# RGBtlc.net
KiCad netlist of a schematic drawn in EAGLE
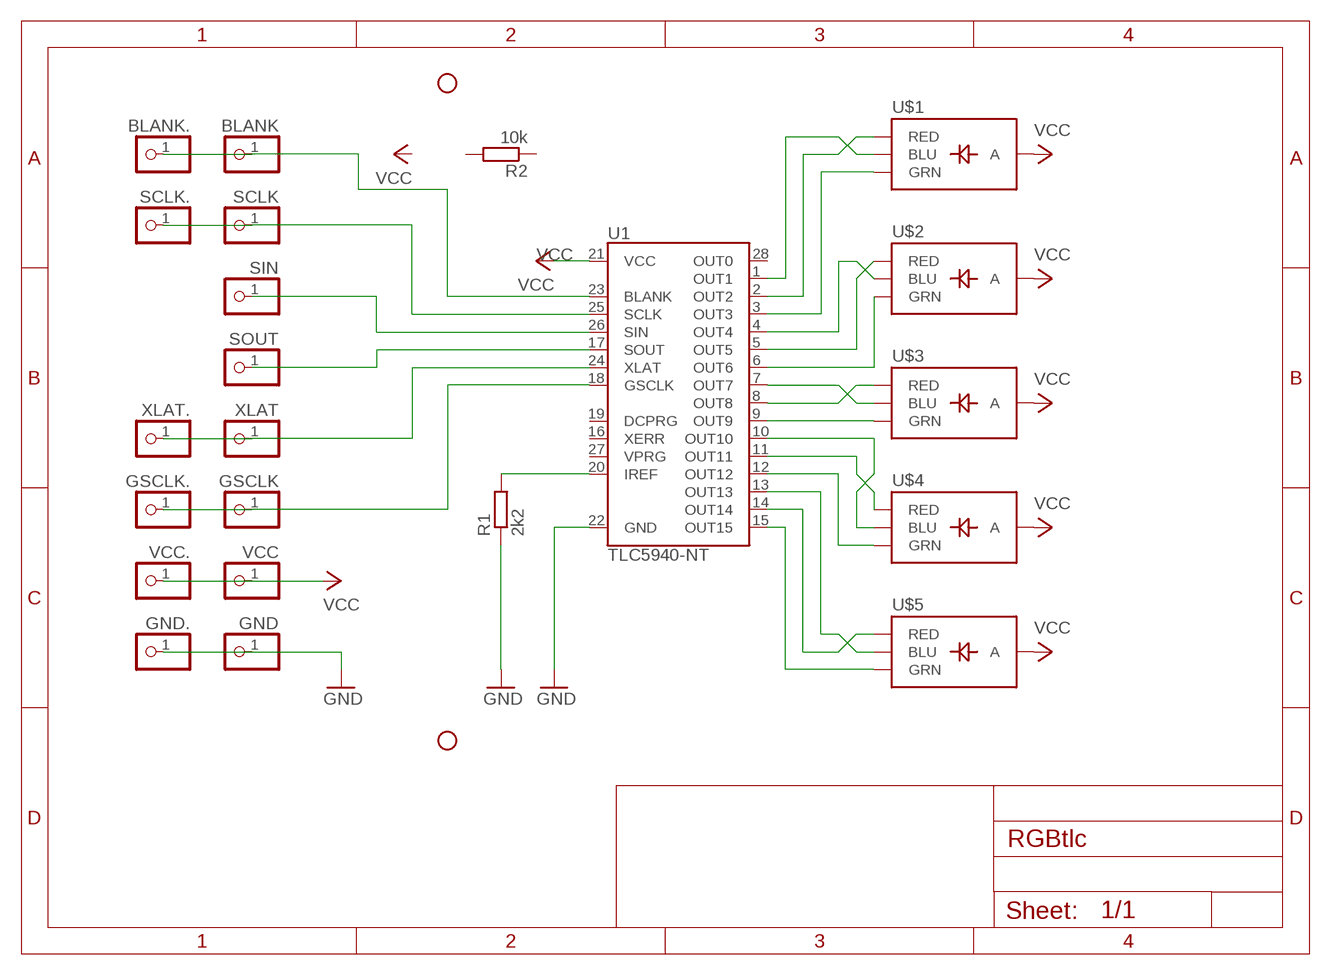
[diagram p0: schematic, sheet 1]

(export (version "E")
  (design (tool "Eeschema 10.0.6"))
  (components
    (comp (ref "BLANK")
      (value "PINHD-1X1")
      (footprint "eagle-import:1X01")
      (libsource (lib "eagle-import") (part "PINHD-1X1"))
    )
    (comp (ref "BLANK.")
      (value "PINHD-1X1")
      (footprint "eagle-import:1X01")
      (libsource (lib "eagle-import") (part "PINHD-1X1"))
    )
    (comp (ref "GND")
      (value "PINHD-1X1")
      (footprint "eagle-import:1X01")
      (libsource (lib "eagle-import") (part "PINHD-1X1"))
    )
    (comp (ref "GND.")
      (value "PINHD-1X1")
      (footprint "eagle-import:1X01")
      (libsource (lib "eagle-import") (part "PINHD-1X1"))
    )
    (comp (ref "GSCLK")
      (value "PINHD-1X1")
      (footprint "eagle-import:1X01")
      (libsource (lib "eagle-import") (part "PINHD-1X1"))
    )
    (comp (ref "GSCLK.")
      (value "PINHD-1X1")
      (footprint "eagle-import:1X01")
      (libsource (lib "eagle-import") (part "PINHD-1X1"))
    )
    (comp (ref "JP1")
      (value "STAND-OFF")
      (footprint "eagle-import:STAND-OFF")
      (libsource (lib "eagle-import") (part "STAND-OFF"))
    )
    (comp (ref "JP4")
      (value "STAND-OFF")
      (footprint "eagle-import:STAND-OFF")
      (libsource (lib "eagle-import") (part "STAND-OFF"))
    )
    (comp (ref "R1")
      (value "2k2")
      (footprint "eagle-import:0207_7")
      (libsource (lib "eagle-import") (part "R-EU_0207/7"))
    )
    (comp (ref "R2")
      (value "10k")
      (footprint "eagle-import:0207_7")
      (libsource (lib "eagle-import") (part "R-EU_0207/7"))
    )
    (comp (ref "SCLK")
      (value "PINHD-1X1")
      (footprint "eagle-import:1X01")
      (libsource (lib "eagle-import") (part "PINHD-1X1"))
    )
    (comp (ref "SCLK.")
      (value "PINHD-1X1")
      (footprint "eagle-import:1X01")
      (libsource (lib "eagle-import") (part "PINHD-1X1"))
    )
    (comp (ref "SIN")
      (value "PINHD-1X1")
      (footprint "eagle-import:1X01")
      (libsource (lib "eagle-import") (part "PINHD-1X1"))
    )
    (comp (ref "SOUT")
      (value "PINHD-1X1")
      (footprint "eagle-import:1X01")
      (libsource (lib "eagle-import") (part "PINHD-1X1"))
    )
    (comp (ref "U$1")
      (value "LED_PIRANHA_5MM")
      (footprint "eagle-import:LED_PIRANHA_5MM")
      (libsource (lib "eagle-import") (part "LED_PIRANHA_5MM"))
    )
    (comp (ref "U$2")
      (value "LED_PIRANHA_5MM")
      (footprint "eagle-import:LED_PIRANHA_5MM")
      (libsource (lib "eagle-import") (part "LED_PIRANHA_5MM"))
    )
    (comp (ref "U$3")
      (value "LED_PIRANHA_5MM")
      (footprint "eagle-import:LED_PIRANHA_5MM")
      (libsource (lib "eagle-import") (part "LED_PIRANHA_5MM"))
    )
    (comp (ref "U$4")
      (value "LED_PIRANHA_5MM")
      (footprint "eagle-import:LED_PIRANHA_5MM")
      (libsource (lib "eagle-import") (part "LED_PIRANHA_5MM"))
    )
    (comp (ref "U$5")
      (value "LED_PIRANHA_5MM")
      (footprint "eagle-import:LED_PIRANHA_5MM")
      (libsource (lib "eagle-import") (part "LED_PIRANHA_5MM"))
    )
    (comp (ref "U1")
      (value "TLC5940-NT")
      (footprint "eagle-import:DIL28-3")
      (libsource (lib "eagle-import") (part "TLC5940-NT"))
    )
    (comp (ref "VCC")
      (value "PINHD-1X1")
      (footprint "eagle-import:1X01")
      (libsource (lib "eagle-import") (part "PINHD-1X1"))
    )
    (comp (ref "VCC.")
      (value "PINHD-1X1")
      (footprint "eagle-import:1X01")
      (libsource (lib "eagle-import") (part "PINHD-1X1"))
    )
    (comp (ref "XLAT")
      (value "PINHD-1X1")
      (footprint "eagle-import:1X01")
      (libsource (lib "eagle-import") (part "PINHD-1X1"))
    )
    (comp (ref "XLAT.")
      (value "PINHD-1X1")
      (footprint "eagle-import:1X01")
      (libsource (lib "eagle-import") (part "PINHD-1X1"))
    )
  )
  (nets
    (net (code "1") (name "GND") (class "Default")
      (node (ref "GND") (pin "1") (pinfunction "1_1") (pintype "passive"))
      (node (ref "GND.") (pin "1") (pinfunction "1_1") (pintype "passive"))
      (node (ref "R1") (pin "1") (pinfunction "1_1") (pintype "passive"))
      (node (ref "U1") (pin "22") (pinfunction "GND_22") (pintype "bidirectional"))
    )
    (net (code "2") (name "Net-(U$1-BLU)") (class "Default")
      (node (ref "U$1") (pin "B") (pinfunction "BLU_B") (pintype "bidirectional"))
      (node (ref "U1") (pin "1") (pinfunction "OUT1_1") (pintype "bidirectional"))
    )
    (net (code "3") (name "Net-(U$1-GRN)") (class "Default")
      (node (ref "U$1") (pin "G") (pinfunction "GRN_G") (pintype "bidirectional"))
      (node (ref "U1") (pin "3") (pinfunction "OUT3_3") (pintype "bidirectional"))
    )
    (net (code "4") (name "Net-(U$1-RED)") (class "Default")
      (node (ref "U$1") (pin "R") (pinfunction "RED_R") (pintype "bidirectional"))
      (node (ref "U1") (pin "2") (pinfunction "OUT2_2") (pintype "bidirectional"))
    )
    (net (code "5") (name "Net-(U$2-BLU)") (class "Default")
      (node (ref "U$2") (pin "B") (pinfunction "BLU_B") (pintype "bidirectional"))
      (node (ref "U1") (pin "4") (pinfunction "OUT4_4") (pintype "bidirectional"))
    )
    (net (code "6") (name "Net-(U$2-GRN)") (class "Default")
      (node (ref "U$2") (pin "G") (pinfunction "GRN_G") (pintype "bidirectional"))
      (node (ref "U1") (pin "6") (pinfunction "OUT6_6") (pintype "bidirectional"))
    )
    (net (code "7") (name "Net-(U$2-RED)") (class "Default")
      (node (ref "U$2") (pin "R") (pinfunction "RED_R") (pintype "bidirectional"))
      (node (ref "U1") (pin "5") (pinfunction "OUT5_5") (pintype "bidirectional"))
    )
    (net (code "8") (name "Net-(U$3-BLU)") (class "Default")
      (node (ref "U$3") (pin "B") (pinfunction "BLU_B") (pintype "bidirectional"))
      (node (ref "U1") (pin "7") (pinfunction "OUT7_7") (pintype "bidirectional"))
    )
    (net (code "9") (name "Net-(U$3-GRN)") (class "Default")
      (node (ref "U$3") (pin "G") (pinfunction "GRN_G") (pintype "bidirectional"))
      (node (ref "U1") (pin "9") (pinfunction "OUT9_9") (pintype "bidirectional"))
    )
    (net (code "10") (name "Net-(U$3-RED)") (class "Default")
      (node (ref "U$3") (pin "R") (pinfunction "RED_R") (pintype "bidirectional"))
      (node (ref "U1") (pin "8") (pinfunction "OUT8_8") (pintype "bidirectional"))
    )
    (net (code "11") (name "Net-(U$4-BLU)") (class "Default")
      (node (ref "U$4") (pin "B") (pinfunction "BLU_B") (pintype "bidirectional"))
      (node (ref "U1") (pin "10") (pinfunction "OUT10_10") (pintype "bidirectional"))
    )
    (net (code "12") (name "Net-(U$4-GRN)") (class "Default")
      (node (ref "U$4") (pin "G") (pinfunction "GRN_G") (pintype "bidirectional"))
      (node (ref "U1") (pin "12") (pinfunction "OUT12_12") (pintype "bidirectional"))
    )
    (net (code "13") (name "Net-(U$4-RED)") (class "Default")
      (node (ref "U$4") (pin "R") (pinfunction "RED_R") (pintype "bidirectional"))
      (node (ref "U1") (pin "11") (pinfunction "OUT11_11") (pintype "bidirectional"))
    )
    (net (code "14") (name "Net-(U$5-BLU)") (class "Default")
      (node (ref "U$5") (pin "B") (pinfunction "BLU_B") (pintype "bidirectional"))
      (node (ref "U1") (pin "13") (pinfunction "OUT13_13") (pintype "bidirectional"))
    )
    (net (code "15") (name "Net-(U$5-GRN)") (class "Default")
      (node (ref "U$5") (pin "G") (pinfunction "GRN_G") (pintype "bidirectional"))
      (node (ref "U1") (pin "15") (pinfunction "OUT15_15") (pintype "bidirectional"))
    )
    (net (code "16") (name "Net-(U$5-RED)") (class "Default")
      (node (ref "U$5") (pin "R") (pinfunction "RED_R") (pintype "bidirectional"))
      (node (ref "U1") (pin "14") (pinfunction "OUT14_14") (pintype "bidirectional"))
    )
    (net (code "17") (name "Net-(U1-BLANK)") (class "Default")
      (node (ref "BLANK") (pin "1") (pinfunction "1_1") (pintype "passive"))
      (node (ref "BLANK.") (pin "1") (pinfunction "1_1") (pintype "passive"))
      (node (ref "U1") (pin "23") (pinfunction "BLANK_23") (pintype "bidirectional"))
    )
    (net (code "18") (name "Net-(U1-GSCLK)") (class "Default")
      (node (ref "GSCLK") (pin "1") (pinfunction "1_1") (pintype "passive"))
      (node (ref "GSCLK.") (pin "1") (pinfunction "1_1") (pintype "passive"))
      (node (ref "U1") (pin "18") (pinfunction "GSCLK_18") (pintype "bidirectional"))
    )
    (net (code "19") (name "Net-(U1-IREF)") (class "Default")
      (node (ref "R1") (pin "2") (pinfunction "2_2") (pintype "passive"))
      (node (ref "U1") (pin "20") (pinfunction "IREF_20") (pintype "bidirectional"))
    )
    (net (code "20") (name "Net-(U1-SCLK)") (class "Default")
      (node (ref "SCLK") (pin "1") (pinfunction "1_1") (pintype "passive"))
      (node (ref "SCLK.") (pin "1") (pinfunction "1_1") (pintype "passive"))
      (node (ref "U1") (pin "25") (pinfunction "SCLK_25") (pintype "bidirectional"))
    )
    (net (code "21") (name "Net-(U1-SIN)") (class "Default")
      (node (ref "SIN") (pin "1") (pinfunction "1_1") (pintype "passive"))
      (node (ref "U1") (pin "26") (pinfunction "SIN_26") (pintype "bidirectional"))
    )
    (net (code "22") (name "Net-(U1-SOUT)") (class "Default")
      (node (ref "SOUT") (pin "1") (pinfunction "1_1") (pintype "passive"))
      (node (ref "U1") (pin "17") (pinfunction "SOUT_17") (pintype "bidirectional"))
    )
    (net (code "23") (name "Net-(U1-XLAT)") (class "Default")
      (node (ref "U1") (pin "24") (pinfunction "XLAT_24") (pintype "bidirectional"))
      (node (ref "XLAT") (pin "1") (pinfunction "1_1") (pintype "passive"))
      (node (ref "XLAT.") (pin "1") (pinfunction "1_1") (pintype "passive"))
    )
    (net (code "24") (name "VCC") (class "Default")
      (node (ref "U$1") (pin "+") (pinfunction "A_+") (pintype "bidirectional"))
      (node (ref "U$2") (pin "+") (pinfunction "A_+") (pintype "bidirectional"))
      (node (ref "U$3") (pin "+") (pinfunction "A_+") (pintype "bidirectional"))
      (node (ref "U$4") (pin "+") (pinfunction "A_+") (pintype "bidirectional"))
      (node (ref "U$5") (pin "+") (pinfunction "A_+") (pintype "bidirectional"))
      (node (ref "U1") (pin "21") (pinfunction "VCC_21") (pintype "bidirectional"))
      (node (ref "VCC") (pin "1") (pinfunction "1_1") (pintype "passive"))
      (node (ref "VCC.") (pin "1") (pinfunction "1_1") (pintype "passive"))
    )
    (net (code "25") (name "unconnected-(R2-Pad1)") (class "Default")
      (node (ref "R2") (pin "1") (pinfunction "1_1") (pintype "passive"))
    )
    (net (code "26") (name "unconnected-(R2-Pad2)") (class "Default")
      (node (ref "R2") (pin "2") (pinfunction "2_2") (pintype "passive"))
    )
    (net (code "27") (name "unconnected-(U1-DCPRG-Pad19)") (class "Default")
      (node (ref "U1") (pin "19") (pinfunction "DCPRG_19") (pintype "bidirectional"))
    )
    (net (code "28") (name "unconnected-(U1-OUT0-Pad28)") (class "Default")
      (node (ref "U1") (pin "28") (pinfunction "OUT0_28") (pintype "bidirectional"))
    )
    (net (code "29") (name "unconnected-(U1-VPRG-Pad27)") (class "Default")
      (node (ref "U1") (pin "27") (pinfunction "VPRG_27") (pintype "bidirectional"))
    )
    (net (code "30") (name "unconnected-(U1-XERR-Pad16)") (class "Default")
      (node (ref "U1") (pin "16") (pinfunction "XERR_16") (pintype "bidirectional"))
    )
  )
)
